# 467444_130_3_2.net
KiCad netlist of a schematic drawn in Altium Designer
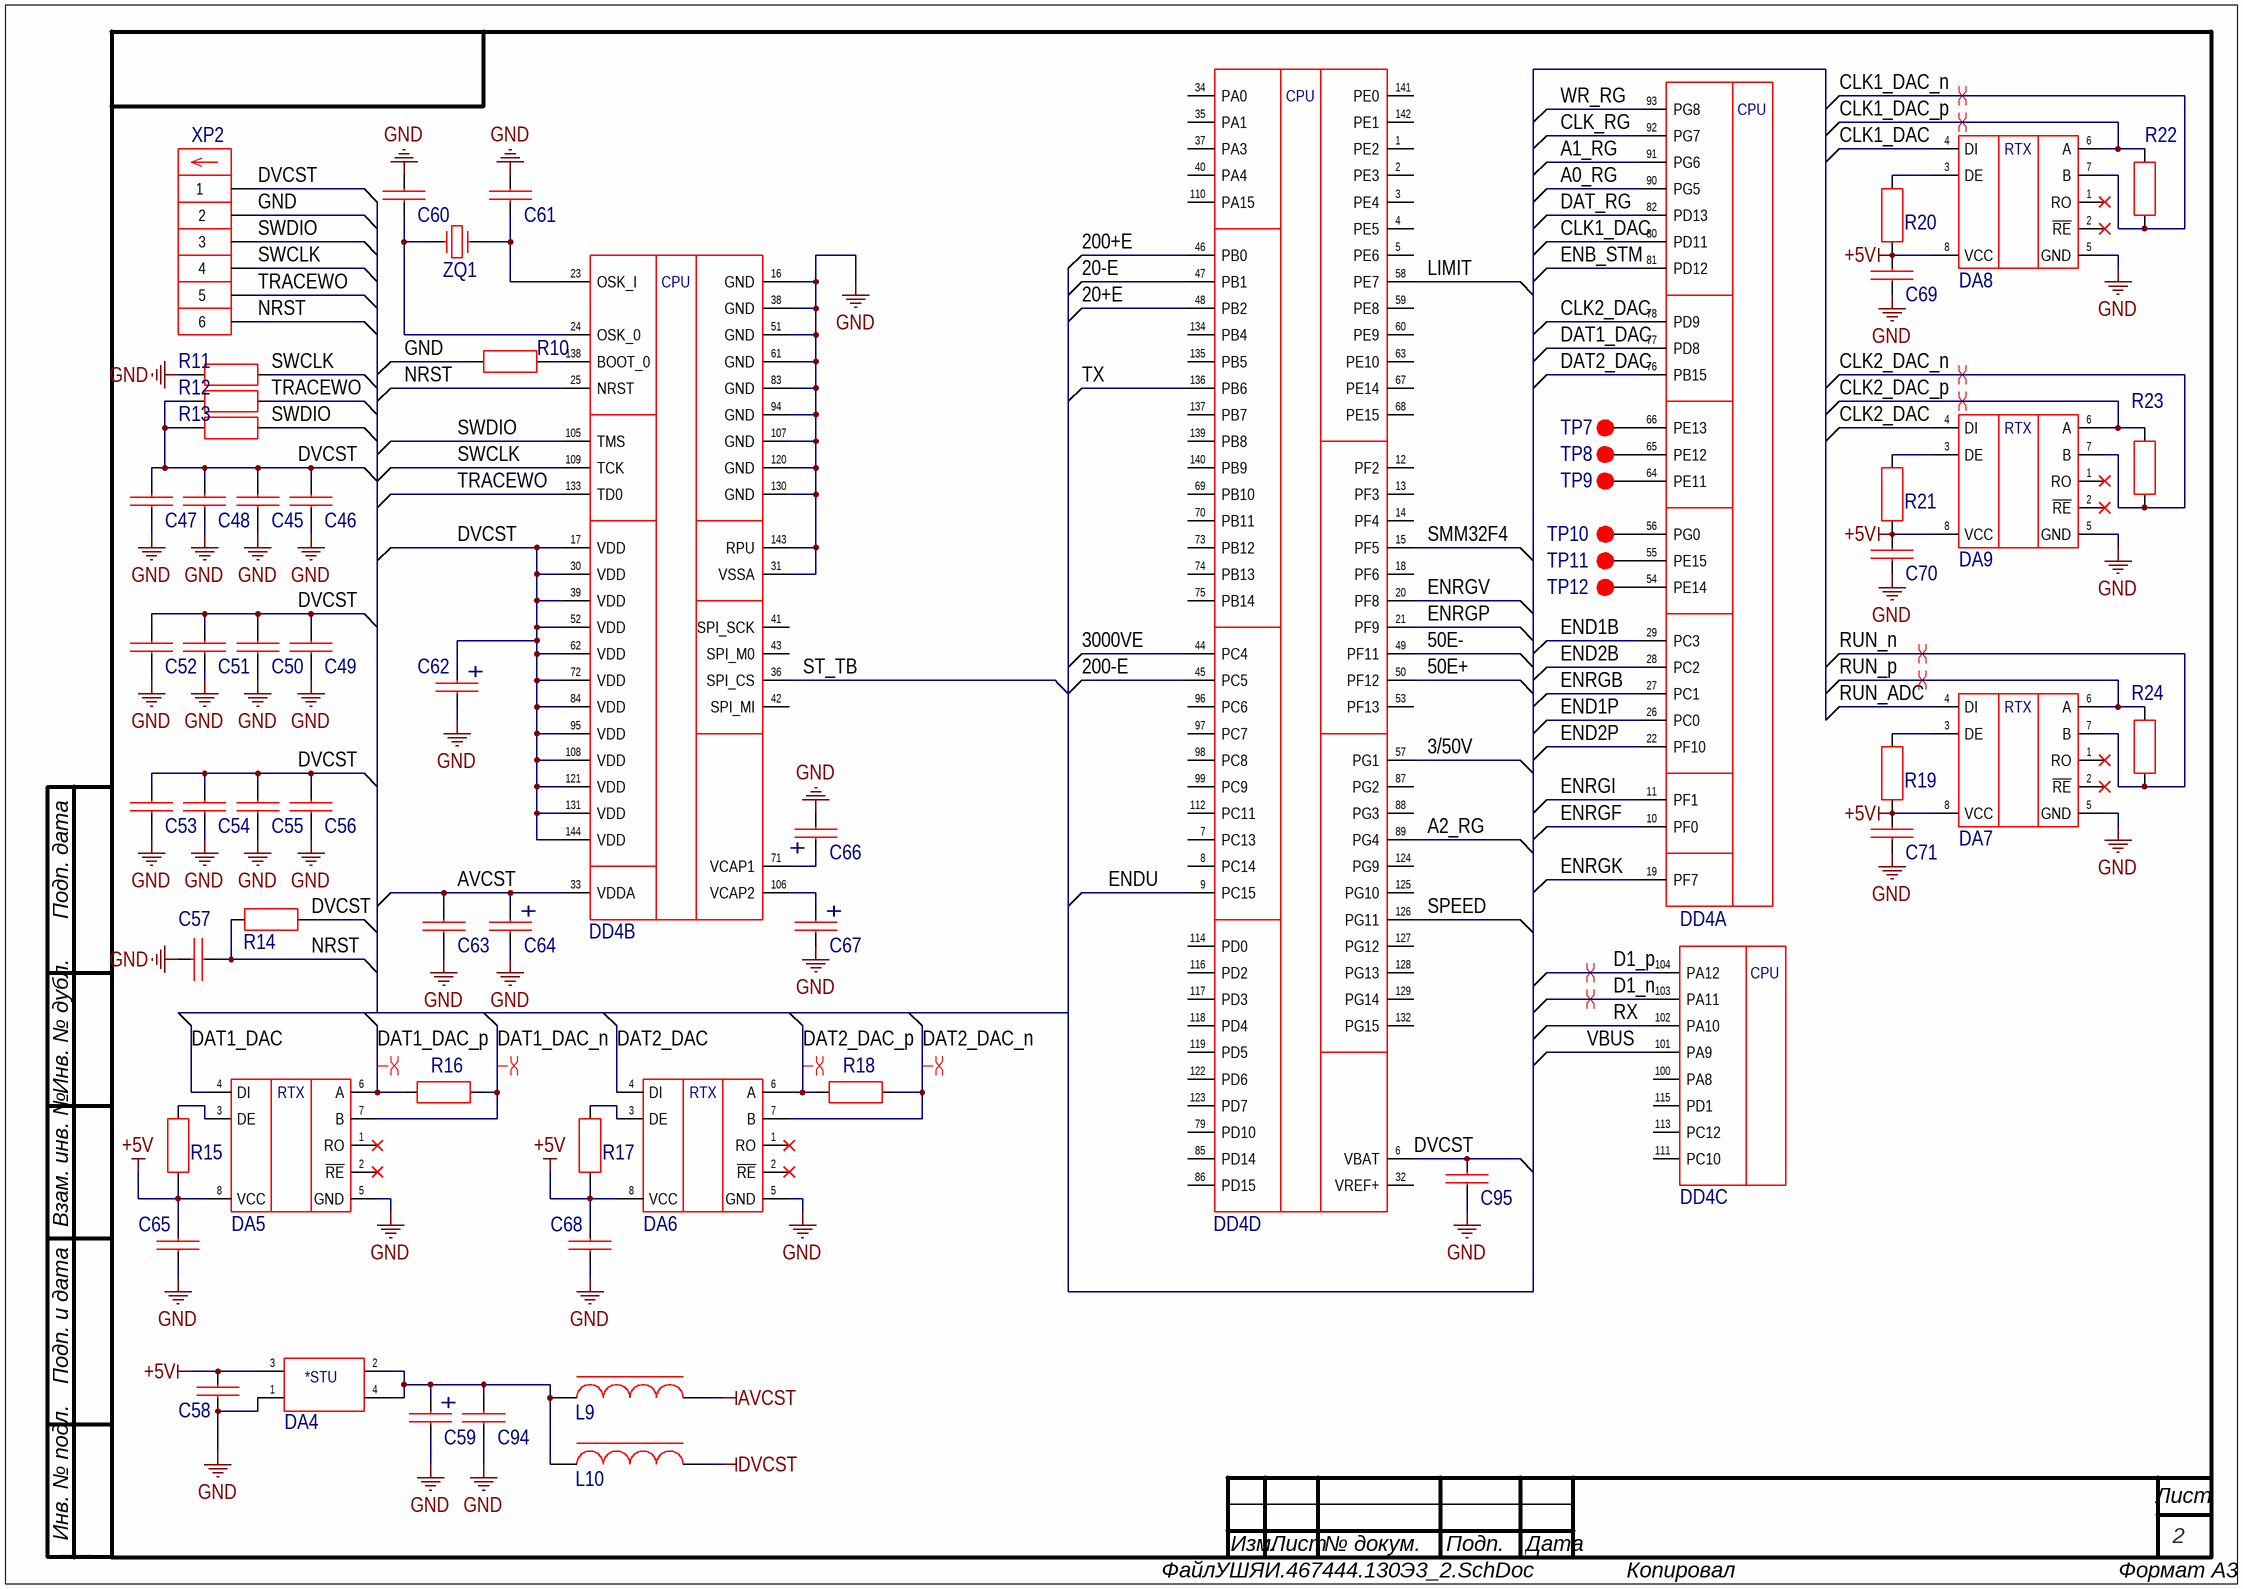
[diagram p0: УШЯИ.467444.130Э3_2.SchDoc]

(export (version "E")
  (design (tool "Eeschema 10.0.6"))
  (components
    (comp (ref "C45")
      (value "0,1 µF")
      (footprint "C_0805 [2012 Metric]")
      (description "Неполярный конденсатор")
      (fields (field (name "MANUFACTURER") "Murata") (field (name "VOLTAGE") "50V"))
      (libsource (lib "lib") (part "C_const"))
    )
    (comp (ref "C46")
      (value "0,1 µF")
      (footprint "C_0805 [2012 Metric]")
      (description "Неполярный конденсатор")
      (fields (field (name "MANUFACTURER") "Murata") (field (name "VOLTAGE") "50V"))
      (libsource (lib "lib") (part "C_const"))
    )
    (comp (ref "C47")
      (value "0,1 µF")
      (footprint "C_0805 [2012 Metric]")
      (description "Неполярный конденсатор")
      (fields (field (name "MANUFACTURER") "Murata") (field (name "VOLTAGE") "50V"))
      (libsource (lib "lib") (part "C_const"))
    )
    (comp (ref "C48")
      (value "0,1 µF")
      (footprint "C_0805 [2012 Metric]")
      (description "Неполярный конденсатор")
      (fields (field (name "MANUFACTURER") "Murata") (field (name "VOLTAGE") "50V"))
      (libsource (lib "lib") (part "C_const"))
    )
    (comp (ref "C49")
      (value "0,1 µF")
      (footprint "C_0805 [2012 Metric]")
      (description "Неполярный конденсатор")
      (fields (field (name "MANUFACTURER") "Murata") (field (name "VOLTAGE") "50V"))
      (libsource (lib "lib") (part "C_const"))
    )
    (comp (ref "C50")
      (value "0,1 µF")
      (footprint "C_0805 [2012 Metric]")
      (description "Неполярный конденсатор")
      (fields (field (name "MANUFACTURER") "Murata") (field (name "VOLTAGE") "50V"))
      (libsource (lib "lib") (part "C_const"))
    )
    (comp (ref "C51")
      (value "0,1 µF")
      (footprint "C_0805 [2012 Metric]")
      (description "Неполярный конденсатор")
      (fields (field (name "MANUFACTURER") "Murata") (field (name "VOLTAGE") "50V"))
      (libsource (lib "lib") (part "C_const"))
    )
    (comp (ref "C52")
      (value "0,1 µF")
      (footprint "C_0805 [2012 Metric]")
      (description "Неполярный конденсатор")
      (fields (field (name "MANUFACTURER") "Murata") (field (name "VOLTAGE") "50V"))
      (libsource (lib "lib") (part "C_const"))
    )
    (comp (ref "C53")
      (value "0,1 µF")
      (footprint "C_0805 [2012 Metric]")
      (description "Неполярный конденсатор")
      (fields (field (name "MANUFACTURER") "Murata") (field (name "VOLTAGE") "50V"))
      (libsource (lib "lib") (part "C_const"))
    )
    (comp (ref "C54")
      (value "0,1 µF")
      (footprint "C_0805 [2012 Metric]")
      (description "Неполярный конденсатор")
      (fields (field (name "MANUFACTURER") "Murata") (field (name "VOLTAGE") "50V"))
      (libsource (lib "lib") (part "C_const"))
    )
    (comp (ref "C55")
      (value "0,1 µF")
      (footprint "C_0805 [2012 Metric]")
      (description "Неполярный конденсатор")
      (fields (field (name "MANUFACTURER") "Murata") (field (name "VOLTAGE") "50V"))
      (libsource (lib "lib") (part "C_const"))
    )
    (comp (ref "C56")
      (value "0,1 µF")
      (footprint "C_0805 [2012 Metric]")
      (description "Неполярный конденсатор")
      (fields (field (name "MANUFACTURER") "Murata") (field (name "VOLTAGE") "50V"))
      (libsource (lib "lib") (part "C_const"))
    )
    (comp (ref "C57")
      (value "0,1 µF")
      (footprint "C_0805 [2012 Metric]")
      (description "Неполярный конденсатор")
      (fields (field (name "MANUFACTURER") "Murata") (field (name "VOLTAGE") "50V"))
      (libsource (lib "lib") (part "C_const"))
    )
    (comp (ref "C58")
      (value "0,1 µF")
      (footprint "C_0805 [2012 Metric]")
      (description "Неполярный конденсатор")
      (fields (field (name "MANUFACTURER") "Murata") (field (name "VOLTAGE") "50V"))
      (libsource (lib "lib") (part "C_const"))
    )
    (comp (ref "C59")
      (value "4,7 µF")
      (footprint "C+_1210 [3528-21 Metric]")
      (description "Полярный конденсатор")
      (fields (field (name "MANUFACTURER") "KYOCERA AVX") (field (name "VOLTAGE") "20V\r\n10V"))
      (libsource (lib "lib") (part "C_electrolytic"))
    )
    (comp (ref "C60")
      (value "20 pF")
      (footprint "C_0805 [2012 Metric]")
      (description "Неполярный конденсатор")
      (fields (field (name "MANUFACTURER") "Murata") (field (name "VOLTAGE") "50V"))
      (libsource (lib "lib") (part "C_const"))
    )
    (comp (ref "C61")
      (value "20 pF")
      (footprint "C_0805 [2012 Metric]")
      (description "Неполярный конденсатор")
      (fields (field (name "MANUFACTURER") "Murata") (field (name "VOLTAGE") "50V"))
      (libsource (lib "lib") (part "C_const"))
    )
    (comp (ref "C62")
      (value "10 µF")
      (footprint "C+_1210 [3528-21 Metric]")
      (description "Полярный конденсатор")
      (fields (field (name "MANUFACTURER") "KYOCERA AVX") (field (name "VOLTAGE") "20V\r\n10V"))
      (libsource (lib "lib") (part "C_electrolytic"))
    )
    (comp (ref "C63")
      (value "0,1 µF")
      (footprint "C_0805 [2012 Metric]")
      (description "Неполярный конденсатор")
      (fields (field (name "MANUFACTURER") "Murata") (field (name "VOLTAGE") "50V"))
      (libsource (lib "lib") (part "C_const"))
    )
    (comp (ref "C64")
      (value "10 µF")
      (footprint "C+_1210 [3528-21 Metric]")
      (description "Полярный конденсатор")
      (fields (field (name "MANUFACTURER") "KYOCERA AVX") (field (name "VOLTAGE") "20V\r\n10V"))
      (libsource (lib "lib") (part "C_electrolytic"))
    )
    (comp (ref "C65")
      (value "0,1 µF")
      (footprint "C_0805 [2012 Metric]")
      (description "Неполярный конденсатор")
      (fields (field (name "MANUFACTURER") "Murata") (field (name "VOLTAGE") "50V"))
      (libsource (lib "lib") (part "C_const"))
    )
    (comp (ref "C66")
      (value "2,2 µF")
      (footprint "C+_1206 [3216-18 Metric]")
      (description "Полярный конденсатор")
      (fields (field (name "MANUFACTURER") "AVX") (field (name "VOLTAGE") "16V\r\n10V"))
      (libsource (lib "lib") (part "C_electrolytic"))
    )
    (comp (ref "C67")
      (value "2,2 µF")
      (footprint "C+_1206 [3216-18 Metric]")
      (description "Полярный конденсатор")
      (fields (field (name "MANUFACTURER") "AVX") (field (name "VOLTAGE") "16V\r\n10V"))
      (libsource (lib "lib") (part "C_electrolytic"))
    )
    (comp (ref "C68")
      (value "0,1 µF")
      (footprint "C_0805 [2012 Metric]")
      (description "Неполярный конденсатор")
      (fields (field (name "MANUFACTURER") "Murata") (field (name "VOLTAGE") "50V"))
      (libsource (lib "lib") (part "C_const"))
    )
    (comp (ref "C69")
      (value "0,1 µF")
      (footprint "C_0805 [2012 Metric]")
      (description "Неполярный конденсатор")
      (fields (field (name "MANUFACTURER") "Murata") (field (name "VOLTAGE") "50V"))
      (libsource (lib "lib") (part "C_const"))
    )
    (comp (ref "C70")
      (value "0,1 µF")
      (footprint "C_0805 [2012 Metric]")
      (description "Неполярный конденсатор")
      (fields (field (name "MANUFACTURER") "Murata") (field (name "VOLTAGE") "50V"))
      (libsource (lib "lib") (part "C_const"))
    )
    (comp (ref "C71")
      (value "0,1 µF")
      (footprint "C_0805 [2012 Metric]")
      (description "Неполярный конденсатор")
      (fields (field (name "MANUFACTURER") "Murata") (field (name "VOLTAGE") "50V"))
      (libsource (lib "lib") (part "C_const"))
    )
    (comp (ref "C94")
      (value "0,1 µF")
      (footprint "C_0805 [2012 Metric]")
      (description "Неполярный конденсатор")
      (fields (field (name "MANUFACTURER") "Murata") (field (name "VOLTAGE") "25V"))
      (libsource (lib "lib") (part "C_const"))
    )
    (comp (ref "C95")
      (value "0,1 µF")
      (footprint "C_0805 [2012 Metric]")
      (description "Неполярный конденсатор")
      (fields (field (name "MANUFACTURER") "Murata") (field (name "VOLTAGE") "50V"))
      (libsource (lib "lib") (part "C_const"))
    )
    (comp (ref "DA4")
      (value "LD1117AS33TR")
      (footprint "SOT-223")
      (description "IC, Fixed LDO Voltage Regulator, 5.3V to 10V, 1.15V Dropout, 3.3Vout, 1Aout")
      (fields (field (name "MANUFACTURER") "STMicroelectronics"))
      (libsource (lib "lib") (part "VolReg_LD1117AS33TR"))
    )
    (comp (ref "DA5")
      (value "ADM483AR")
      (footprint "SOIC-8_1.27_5x4x1.75")
      (description "IC, Transceiver, RS422/RS485, 1 Driver, 1 Receiver, 4.75 V to 5.25 V, -40°C to 125°C")
      (fields (field (name "MANUFACTURER") "Analog Devices"))
      (libsource (lib "lib") (part "ADM483"))
    )
    (comp (ref "DA6")
      (value "ADM483AR")
      (footprint "SOIC-8_1.27_5x4x1.75")
      (description "IC, Transceiver, RS422/RS485, 1 Driver, 1 Receiver, 4.75 V to 5.25 V, -40°C to 125°C")
      (fields (field (name "MANUFACTURER") "Analog Devices"))
      (libsource (lib "lib") (part "ADM483"))
    )
    (comp (ref "DA7")
      (value "ADM483AR")
      (footprint "SOIC-8_1.27_5x4x1.75")
      (description "IC, Transceiver, RS422/RS485, 1 Driver, 1 Receiver, 4.75 V to 5.25 V, -40°C to 125°C")
      (fields (field (name "MANUFACTURER") "Analog Devices"))
      (libsource (lib "lib") (part "ADM483"))
    )
    (comp (ref "DA8")
      (value "ADM483AR")
      (footprint "SOIC-8_1.27_5x4x1.75")
      (description "IC, Transceiver, RS422/RS485, 1 Driver, 1 Receiver, 4.75 V to 5.25 V, -40°C to 125°C")
      (fields (field (name "MANUFACTURER") "Analog Devices"))
      (libsource (lib "lib") (part "ADM483"))
    )
    (comp (ref "DA9")
      (value "ADM483AR")
      (footprint "SOIC-8_1.27_5x4x1.75")
      (description "IC, Transceiver, RS422/RS485, 1 Driver, 1 Receiver, 4.75 V to 5.25 V, -40°C to 125°C")
      (fields (field (name "MANUFACTURER") "Analog Devices"))
      (libsource (lib "lib") (part "ADM483"))
    )
    (comp (ref "DD4")
      (value "STM32F429VIT6STM32F407ZGTx")
      (footprint "QFP-144[20x20]_0.5_22x22x1.6")
      (description "IC, ARM Cortex-M4, 168 MHz, 1 MB ROM, 192 kB RAM, -40°C to 85°C")
      (fields (field (name "MANUFACTURER") "STMicroelectronics"))
      (libsource (lib "") (part "STM32F407_1"))
    )
    (comp (ref "L9")
      (value "~")
      (footprint "IND_0805 [2012 Metric]")
      (fields (field (name "MANUFACTURER") "Vishay") (field (name "TOLERANCE") "±25%"))
      (libsource (lib "lib") (part "IND_ferromagnetic/ferrite_core"))
    )
    (comp (ref "L10")
      (value "~")
      (footprint "IND_0805 [2012 Metric]")
      (fields (field (name "MANUFACTURER") "Vishay") (field (name "TOLERANCE") "±25%"))
      (libsource (lib "lib") (part "IND_ferromagnetic/ferrite_core"))
    )
    (comp (ref "R10")
      (value "10k")
      (footprint "R_0805 [2012 Metric]")
      (fields (field (name "TOLERANCE") "±5%"))
      (libsource (lib "lib") (part "R_Const"))
    )
    (comp (ref "R11")
      (value "10k")
      (footprint "R_0805 [2012 Metric]")
      (fields (field (name "TOLERANCE") "±5%"))
      (libsource (lib "lib") (part "R_Const"))
    )
    (comp (ref "R12")
      (value "10k")
      (footprint "R_0805 [2012 Metric]")
      (fields (field (name "TOLERANCE") "±5%"))
      (libsource (lib "lib") (part "R_Const"))
    )
    (comp (ref "R13")
      (value "10k")
      (footprint "R_0805 [2012 Metric]")
      (fields (field (name "TOLERANCE") "±5%"))
      (libsource (lib "lib") (part "R_Const"))
    )
    (comp (ref "R14")
      (value "10k")
      (footprint "R_0805 [2012 Metric]")
      (fields (field (name "TOLERANCE") "±5%"))
      (libsource (lib "lib") (part "R_Const"))
    )
    (comp (ref "R15")
      (value "10k")
      (footprint "R_0805 [2012 Metric]")
      (fields (field (name "TOLERANCE") "±5%"))
      (libsource (lib "lib") (part "R_Const"))
    )
    (comp (ref "R16")
      (value "100R")
      (footprint "R_0805 [2012 Metric]")
      (fields (field (name "TOLERANCE") "±5%"))
      (libsource (lib "lib") (part "R_Const"))
    )
    (comp (ref "R17")
      (value "10k")
      (footprint "R_0805 [2012 Metric]")
      (fields (field (name "TOLERANCE") "±5%"))
      (libsource (lib "lib") (part "R_Const"))
    )
    (comp (ref "R18")
      (value "100R")
      (footprint "R_0805 [2012 Metric]")
      (fields (field (name "TOLERANCE") "±5%"))
      (libsource (lib "lib") (part "R_Const"))
    )
    (comp (ref "R19")
      (value "10k")
      (footprint "R_0805 [2012 Metric]")
      (fields (field (name "TOLERANCE") "±5%"))
      (libsource (lib "lib") (part "R_Const"))
    )
    (comp (ref "R20")
      (value "10k")
      (footprint "R_0805 [2012 Metric]")
      (fields (field (name "TOLERANCE") "±5%"))
      (libsource (lib "lib") (part "R_Const"))
    )
    (comp (ref "R21")
      (value "10k")
      (footprint "R_0805 [2012 Metric]")
      (fields (field (name "TOLERANCE") "±5%"))
      (libsource (lib "lib") (part "R_Const"))
    )
    (comp (ref "R22")
      (value "100R")
      (footprint "R_0805 [2012 Metric]")
      (fields (field (name "TOLERANCE") "±5%"))
      (libsource (lib "lib") (part "R_Const"))
    )
    (comp (ref "R23")
      (value "100R")
      (footprint "R_0805 [2012 Metric]")
      (fields (field (name "TOLERANCE") "±5%"))
      (libsource (lib "lib") (part "R_Const"))
    )
    (comp (ref "R24")
      (value "100R")
      (footprint "R_0805 [2012 Metric]")
      (fields (field (name "TOLERANCE") "±5%"))
      (libsource (lib "lib") (part "R_Const"))
    )
    (comp (ref "TP7") (value "~") (footprint "DSP_1.3") (libsource (lib "lib") (part "TP")))
    (comp (ref "TP8") (value "~") (footprint "DSP_1.3") (libsource (lib "lib") (part "TP")))
    (comp (ref "TP9") (value "~") (footprint "DSP_1.3") (libsource (lib "lib") (part "TP")))
    (comp (ref "TP10") (value "~") (footprint "DSP_1.3") (libsource (lib "lib") (part "TP")))
    (comp (ref "TP11") (value "~") (footprint "DSP_1.3") (libsource (lib "lib") (part "TP")))
    (comp (ref "TP12") (value "~") (footprint "DSP_1.3") (libsource (lib "lib") (part "TP")))
    (comp (ref "XP2")
      (value "AMPMODU II 280372-2")
      (footprint "AMP II-280372-2")
      (description "Male, 6 pin, 1 row, Vertical, Board-to-Board, 2.54 mm")
      (fields (field (name "MANUFACTURER") "TE Connectivity"))
      (libsource (lib "lib") (part "M_6"))
    )
    (comp (ref "ZQ1")
      (value "Q 25.0JXS63-12-30/30-FU")
      (footprint "JXS63")
      (fields (field (name "MANUFACTURER") "Jauch Quartz GmbH"))
      (libsource (lib "lib") (part "Rezonator_JXS63"))
    )
  )
  (nets
    (net (code "1") (name "+5V") (class "Default")
      (node (ref "C58") (pin "1") (pinfunction "1_1") (pintype "passive"))
      (node (ref "C65") (pin "2") (pinfunction "2_2") (pintype "passive"))
      (node (ref "C68") (pin "2") (pinfunction "2_2") (pintype "passive"))
      (node (ref "C69") (pin "2") (pinfunction "2_2") (pintype "passive"))
      (node (ref "C70") (pin "2") (pinfunction "2_2") (pintype "passive"))
      (node (ref "C71") (pin "2") (pinfunction "2_2") (pintype "passive"))
      (node (ref "DA4") (pin "3") (pinfunction "VIN_3") (pintype "passive"))
      (node (ref "DA5") (pin "8") (pinfunction "VCC_8") (pintype "passive"))
      (node (ref "DA6") (pin "8") (pinfunction "VCC_8") (pintype "passive"))
      (node (ref "DA7") (pin "8") (pinfunction "VCC_8") (pintype "passive"))
      (node (ref "DA8") (pin "8") (pinfunction "VCC_8") (pintype "passive"))
      (node (ref "DA9") (pin "8") (pinfunction "VCC_8") (pintype "passive"))
      (node (ref "R15") (pin "1") (pinfunction "1_1") (pintype "passive"))
      (node (ref "R17") (pin "1") (pinfunction "1_1") (pintype "passive"))
      (node (ref "R19") (pin "1") (pinfunction "1_1") (pintype "passive"))
      (node (ref "R20") (pin "1") (pinfunction "1_1") (pintype "passive"))
      (node (ref "R21") (pin "1") (pinfunction "1_1") (pintype "passive"))
    )
    (net (code "2") (name "/3{slash}50V") (class "Default")
      (node (ref "DD4") (pin "57") (pinfunction "PG1_57") (pintype "passive"))
    )
    (net (code "3") (name "/20+E") (class "Default")
      (node (ref "DD4") (pin "48") (pinfunction "PB2_48") (pintype "passive"))
    )
    (net (code "4") (name "/20-E") (class "Default")
      (node (ref "DD4") (pin "47") (pinfunction "PB1_47") (pintype "passive"))
    )
    (net (code "5") (name "/50E+") (class "Default")
      (node (ref "DD4") (pin "50") (pinfunction "PF12_50") (pintype "passive"))
    )
    (net (code "6") (name "/50E-") (class "Default")
      (node (ref "DD4") (pin "49") (pinfunction "PF11_49") (pintype "passive"))
    )
    (net (code "7") (name "/200+E") (class "Default")
      (node (ref "DD4") (pin "46") (pinfunction "PB0_46") (pintype "passive"))
    )
    (net (code "8") (name "/200-E") (class "Default")
      (node (ref "DD4") (pin "45") (pinfunction "PC5_45") (pintype "passive"))
    )
    (net (code "9") (name "/3000VE") (class "Default")
      (node (ref "DD4") (pin "44") (pinfunction "PC4_44") (pintype "passive"))
    )
    (net (code "10") (name "/A0_RG") (class "Default")
      (node (ref "DD4") (pin "90") (pinfunction "PG5_90") (pintype "passive"))
    )
    (net (code "11") (name "/A1_RG") (class "Default")
      (node (ref "DD4") (pin "91") (pinfunction "PG6_91") (pintype "passive"))
    )
    (net (code "12") (name "/A2_RG") (class "Default")
      (node (ref "DD4") (pin "89") (pinfunction "PG4_89") (pintype "passive"))
    )
    (net (code "13") (name "/CLK1_DAC") (class "Default")
      (node (ref "DA8") (pin "4") (pinfunction "DI_4") (pintype "passive"))
      (node (ref "DD4") (pin "80") (pinfunction "PD11_80") (pintype "passive"))
    )
    (net (code "14") (name "/CLK1_DAC_n") (class "Default")
      (node (ref "DA8") (pin "7") (pinfunction "B_7") (pintype "passive"))
      (node (ref "R22") (pin "1") (pinfunction "1_1") (pintype "passive"))
    )
    (net (code "15") (name "/CLK1_DAC_p") (class "Default")
      (node (ref "DA8") (pin "6") (pinfunction "A_6") (pintype "passive"))
      (node (ref "R22") (pin "2") (pinfunction "2_2") (pintype "passive"))
    )
    (net (code "16") (name "/CLK2_DAC") (class "Default")
      (node (ref "DA9") (pin "4") (pinfunction "DI_4") (pintype "passive"))
      (node (ref "DD4") (pin "78") (pinfunction "PD9_78") (pintype "passive"))
    )
    (net (code "17") (name "/CLK2_DAC_n") (class "Default")
      (node (ref "DA9") (pin "7") (pinfunction "B_7") (pintype "passive"))
      (node (ref "R23") (pin "1") (pinfunction "1_1") (pintype "passive"))
    )
    (net (code "18") (name "/CLK2_DAC_p") (class "Default")
      (node (ref "DA9") (pin "6") (pinfunction "A_6") (pintype "passive"))
      (node (ref "R23") (pin "2") (pinfunction "2_2") (pintype "passive"))
    )
    (net (code "19") (name "/CLK_RG") (class "Default")
      (node (ref "DD4") (pin "92") (pinfunction "PG7_92") (pintype "passive"))
    )
    (net (code "20") (name "/D1_n") (class "Default")
      (node (ref "DD4") (pin "103") (pinfunction "PA11_103") (pintype "passive"))
    )
    (net (code "21") (name "/D1_p") (class "Default")
      (node (ref "DD4") (pin "104") (pinfunction "PA12_104") (pintype "passive"))
    )
    (net (code "22") (name "/DAT1_DAC") (class "Default")
      (node (ref "DA5") (pin "4") (pinfunction "DI_4") (pintype "passive"))
      (node (ref "DD4") (pin "77") (pinfunction "PD8_77") (pintype "passive"))
    )
    (net (code "23") (name "/DAT1_DAC_n") (class "Default")
      (node (ref "DA5") (pin "7") (pinfunction "B_7") (pintype "passive"))
      (node (ref "R16") (pin "2") (pinfunction "2_2") (pintype "passive"))
    )
    (net (code "24") (name "/DAT1_DAC_p") (class "Default")
      (node (ref "DA5") (pin "6") (pinfunction "A_6") (pintype "passive"))
      (node (ref "R16") (pin "1") (pinfunction "1_1") (pintype "passive"))
    )
    (net (code "25") (name "/DAT2_DAC") (class "Default")
      (node (ref "DA6") (pin "4") (pinfunction "DI_4") (pintype "passive"))
      (node (ref "DD4") (pin "76") (pinfunction "PB15_76") (pintype "passive"))
    )
    (net (code "26") (name "/DAT2_DAC_n") (class "Default")
      (node (ref "DA6") (pin "7") (pinfunction "B_7") (pintype "passive"))
      (node (ref "R18") (pin "2") (pinfunction "2_2") (pintype "passive"))
    )
    (net (code "27") (name "/DAT2_DAC_p") (class "Default")
      (node (ref "DA6") (pin "6") (pinfunction "A_6") (pintype "passive"))
      (node (ref "R18") (pin "1") (pinfunction "1_1") (pintype "passive"))
    )
    (net (code "28") (name "/DAT_RG") (class "Default")
      (node (ref "DD4") (pin "82") (pinfunction "PD13_82") (pintype "passive"))
    )
    (net (code "29") (name "/ENB_STM") (class "Default")
      (node (ref "DD4") (pin "81") (pinfunction "PD12_81") (pintype "passive"))
    )
    (net (code "30") (name "/END1B") (class "Default")
      (node (ref "DD4") (pin "29") (pinfunction "PC3_29") (pintype "passive"))
    )
    (net (code "31") (name "/END1P") (class "Default")
      (node (ref "DD4") (pin "26") (pinfunction "PC0_26") (pintype "passive"))
    )
    (net (code "32") (name "/END2B") (class "Default")
      (node (ref "DD4") (pin "28") (pinfunction "PC2_28") (pintype "passive"))
    )
    (net (code "33") (name "/END2P") (class "Default")
      (node (ref "DD4") (pin "22") (pinfunction "PF10_22") (pintype "passive"))
    )
    (net (code "34") (name "/ENDU") (class "Default")
      (node (ref "DD4") (pin "9") (pinfunction "PC15_9") (pintype "passive"))
    )
    (net (code "35") (name "/ENRGB") (class "Default")
      (node (ref "DD4") (pin "27") (pinfunction "PC1_27") (pintype "passive"))
    )
    (net (code "36") (name "/ENRGF") (class "Default")
      (node (ref "DD4") (pin "10") (pinfunction "PF0_10") (pintype "passive"))
    )
    (net (code "37") (name "/ENRGI") (class "Default")
      (node (ref "DD4") (pin "11") (pinfunction "PF1_11") (pintype "passive"))
    )
    (net (code "38") (name "/ENRGK") (class "Default")
      (node (ref "DD4") (pin "19") (pinfunction "PF7_19") (pintype "passive"))
    )
    (net (code "39") (name "/ENRGP") (class "Default")
      (node (ref "DD4") (pin "21") (pinfunction "PF9_21") (pintype "passive"))
    )
    (net (code "40") (name "/ENRGV") (class "Default")
      (node (ref "DD4") (pin "20") (pinfunction "PF8_20") (pintype "passive"))
    )
    (net (code "41") (name "/LIMIT") (class "Default")
      (node (ref "DD4") (pin "58") (pinfunction "PE7_58") (pintype "passive"))
    )
    (net (code "42") (name "/NRST") (class "Default")
      (node (ref "C57") (pin "2") (pinfunction "2_2") (pintype "passive"))
      (node (ref "DD4") (pin "25") (pinfunction "NRST_25") (pintype "passive"))
      (node (ref "R14") (pin "2") (pinfunction "2_2") (pintype "passive"))
      (node (ref "XP2") (pin "6") (pinfunction "6_6") (pintype "passive"))
    )
    (net (code "43") (name "/RUN_ADC") (class "Default")
      (node (ref "DA7") (pin "4") (pinfunction "DI_4") (pintype "passive"))
    )
    (net (code "44") (name "/RUN_n") (class "Default")
      (node (ref "DA7") (pin "7") (pinfunction "B_7") (pintype "passive"))
      (node (ref "R24") (pin "1") (pinfunction "1_1") (pintype "passive"))
    )
    (net (code "45") (name "/RUN_p") (class "Default")
      (node (ref "DA7") (pin "6") (pinfunction "A_6") (pintype "passive"))
      (node (ref "R24") (pin "2") (pinfunction "2_2") (pintype "passive"))
    )
    (net (code "46") (name "/RX") (class "Default")
      (node (ref "DD4") (pin "102") (pinfunction "PA10_102") (pintype "passive"))
    )
    (net (code "47") (name "/SMM32F4") (class "Default")
      (node (ref "DD4") (pin "15") (pinfunction "PF5_15") (pintype "passive"))
    )
    (net (code "48") (name "/SPEED") (class "Default")
      (node (ref "DD4") (pin "126") (pinfunction "PG11_126") (pintype "passive"))
    )
    (net (code "49") (name "/ST_TB") (class "Default")
      (node (ref "DD4") (pin "36") (pinfunction "SPI_CS_36") (pintype "passive"))
    )
    (net (code "50") (name "/SWCLK") (class "Default")
      (node (ref "DD4") (pin "109") (pinfunction "TCK_109") (pintype "passive"))
      (node (ref "R11") (pin "2") (pinfunction "2_2") (pintype "passive"))
      (node (ref "XP2") (pin "4") (pinfunction "4_4") (pintype "passive"))
    )
    (net (code "51") (name "/SWDIO") (class "Default")
      (node (ref "DD4") (pin "105") (pinfunction "TMS_105") (pintype "passive"))
      (node (ref "R13") (pin "2") (pinfunction "2_2") (pintype "passive"))
      (node (ref "XP2") (pin "3") (pinfunction "3_3") (pintype "passive"))
    )
    (net (code "52") (name "/TRACEWO") (class "Default")
      (node (ref "DD4") (pin "133") (pinfunction "TD0_133") (pintype "passive"))
      (node (ref "R12") (pin "2") (pinfunction "2_2") (pintype "passive"))
      (node (ref "XP2") (pin "5") (pinfunction "5_5") (pintype "passive"))
    )
    (net (code "53") (name "/TX") (class "Default")
      (node (ref "DD4") (pin "136") (pinfunction "PB6_136") (pintype "passive"))
    )
    (net (code "54") (name "/VBUS") (class "Default")
      (node (ref "DD4") (pin "101") (pinfunction "PA9_101") (pintype "passive"))
    )
    (net (code "55") (name "/WR_RG") (class "Default")
      (node (ref "DD4") (pin "93") (pinfunction "PG8_93") (pintype "passive"))
    )
    (net (code "56") (name "AVCST") (class "Default")
      (node (ref "C63") (pin "2") (pinfunction "2_2") (pintype "passive"))
      (node (ref "C64") (pin "+") (pinfunction "+_+") (pintype "passive"))
      (node (ref "DD4") (pin "33") (pinfunction "VDDA_33") (pintype "passive"))
      (node (ref "L9") (pin "2") (pinfunction "2_2") (pintype "passive"))
    )
    (net (code "57") (name "DVCST") (class "Default")
      (node (ref "C45") (pin "2") (pinfunction "2_2") (pintype "passive"))
      (node (ref "C46") (pin "2") (pinfunction "2_2") (pintype "passive"))
      (node (ref "C47") (pin "2") (pinfunction "2_2") (pintype "passive"))
      (node (ref "C48") (pin "2") (pinfunction "2_2") (pintype "passive"))
      (node (ref "C49") (pin "2") (pinfunction "2_2") (pintype "passive"))
      (node (ref "C50") (pin "2") (pinfunction "2_2") (pintype "passive"))
      (node (ref "C51") (pin "2") (pinfunction "2_2") (pintype "passive"))
      (node (ref "C52") (pin "2") (pinfunction "2_2") (pintype "passive"))
      (node (ref "C53") (pin "2") (pinfunction "2_2") (pintype "passive"))
      (node (ref "C54") (pin "2") (pinfunction "2_2") (pintype "passive"))
      (node (ref "C55") (pin "2") (pinfunction "2_2") (pintype "passive"))
      (node (ref "C56") (pin "2") (pinfunction "2_2") (pintype "passive"))
      (node (ref "C62") (pin "+") (pinfunction "+_+") (pintype "passive"))
      (node (ref "C95") (pin "2") (pinfunction "2_2") (pintype "passive"))
      (node (ref "DD4") (pin "108") (pinfunction "VDD_108") (pintype "passive"))
      (node (ref "DD4") (pin "121") (pinfunction "VDD_121") (pintype "passive"))
      (node (ref "DD4") (pin "131") (pinfunction "VDD_131") (pintype "passive"))
      (node (ref "DD4") (pin "144") (pinfunction "VDD_144") (pintype "passive"))
      (node (ref "DD4") (pin "17") (pinfunction "VDD_17") (pintype "passive"))
      (node (ref "DD4") (pin "30") (pinfunction "VDD_30") (pintype "passive"))
      (node (ref "DD4") (pin "39") (pinfunction "VDD_39") (pintype "passive"))
      (node (ref "DD4") (pin "52") (pinfunction "VDD_52") (pintype "passive"))
      (node (ref "DD4") (pin "6") (pinfunction "VBAT_6") (pintype "passive"))
      (node (ref "DD4") (pin "62") (pinfunction "VDD_62") (pintype "passive"))
      (node (ref "DD4") (pin "72") (pinfunction "VDD_72") (pintype "passive"))
      (node (ref "DD4") (pin "84") (pinfunction "VDD_84") (pintype "passive"))
      (node (ref "DD4") (pin "95") (pinfunction "VDD_95") (pintype "passive"))
      (node (ref "L10") (pin "2") (pinfunction "2_2") (pintype "passive"))
      (node (ref "R12") (pin "1") (pinfunction "1_1") (pintype "passive"))
      (node (ref "R13") (pin "1") (pinfunction "1_1") (pintype "passive"))
      (node (ref "R14") (pin "1") (pinfunction "1_1") (pintype "passive"))
      (node (ref "XP2") (pin "1") (pinfunction "1_1") (pintype "passive"))
    )
    (net (code "58") (name "GND") (class "Default")
      (node (ref "C45") (pin "1") (pinfunction "1_1") (pintype "passive"))
      (node (ref "C46") (pin "1") (pinfunction "1_1") (pintype "passive"))
      (node (ref "C47") (pin "1") (pinfunction "1_1") (pintype "passive"))
      (node (ref "C48") (pin "1") (pinfunction "1_1") (pintype "passive"))
      (node (ref "C49") (pin "1") (pinfunction "1_1") (pintype "passive"))
      (node (ref "C50") (pin "1") (pinfunction "1_1") (pintype "passive"))
      (node (ref "C51") (pin "1") (pinfunction "1_1") (pintype "passive"))
      (node (ref "C52") (pin "1") (pinfunction "1_1") (pintype "passive"))
      (node (ref "C53") (pin "1") (pinfunction "1_1") (pintype "passive"))
      (node (ref "C54") (pin "1") (pinfunction "1_1") (pintype "passive"))
      (node (ref "C55") (pin "1") (pinfunction "1_1") (pintype "passive"))
      (node (ref "C56") (pin "1") (pinfunction "1_1") (pintype "passive"))
      (node (ref "C57") (pin "1") (pinfunction "1_1") (pintype "passive"))
      (node (ref "C58") (pin "2") (pinfunction "2_2") (pintype "passive"))
      (node (ref "C59") (pin "-") (pinfunction "-_-") (pintype "passive"))
      (node (ref "C60") (pin "2") (pinfunction "2_2") (pintype "passive"))
      (node (ref "C61") (pin "2") (pinfunction "2_2") (pintype "passive"))
      (node (ref "C62") (pin "-") (pinfunction "-_-") (pintype "passive"))
      (node (ref "C63") (pin "1") (pinfunction "1_1") (pintype "passive"))
      (node (ref "C64") (pin "-") (pinfunction "-_-") (pintype "passive"))
      (node (ref "C65") (pin "1") (pinfunction "1_1") (pintype "passive"))
      (node (ref "C66") (pin "-") (pinfunction "-_-") (pintype "passive"))
      (node (ref "C67") (pin "-") (pinfunction "-_-") (pintype "passive"))
      (node (ref "C68") (pin "1") (pinfunction "1_1") (pintype "passive"))
      (node (ref "C69") (pin "1") (pinfunction "1_1") (pintype "passive"))
      (node (ref "C70") (pin "1") (pinfunction "1_1") (pintype "passive"))
      (node (ref "C71") (pin "1") (pinfunction "1_1") (pintype "passive"))
      (node (ref "C94") (pin "1") (pinfunction "1_1") (pintype "passive"))
      (node (ref "C95") (pin "1") (pinfunction "1_1") (pintype "passive"))
      (node (ref "DA4") (pin "1") (pinfunction "ADJ/GND_1") (pintype "passive"))
      (node (ref "DA5") (pin "5") (pinfunction "GND_5") (pintype "passive"))
      (node (ref "DA6") (pin "5") (pinfunction "GND_5") (pintype "passive"))
      (node (ref "DA7") (pin "5") (pinfunction "GND_5") (pintype "passive"))
      (node (ref "DA8") (pin "5") (pinfunction "GND_5") (pintype "passive"))
      (node (ref "DA9") (pin "5") (pinfunction "GND_5") (pintype "passive"))
      (node (ref "DD4") (pin "107") (pinfunction "GND_107") (pintype "passive"))
      (node (ref "DD4") (pin "120") (pinfunction "GND_120") (pintype "passive"))
      (node (ref "DD4") (pin "130") (pinfunction "GND_130") (pintype "passive"))
      (node (ref "DD4") (pin "143") (pinfunction "RPU_143") (pintype "passive"))
      (node (ref "DD4") (pin "16") (pinfunction "GND_16") (pintype "passive"))
      (node (ref "DD4") (pin "31") (pinfunction "VSSA_31") (pintype "passive"))
      (node (ref "DD4") (pin "38") (pinfunction "GND_38") (pintype "passive"))
      (node (ref "DD4") (pin "51") (pinfunction "GND_51") (pintype "passive"))
      (node (ref "DD4") (pin "61") (pinfunction "GND_61") (pintype "passive"))
      (node (ref "DD4") (pin "83") (pinfunction "GND_83") (pintype "passive"))
      (node (ref "DD4") (pin "94") (pinfunction "GND_94") (pintype "passive"))
      (node (ref "R10") (pin "1") (pinfunction "1_1") (pintype "passive"))
      (node (ref "R11") (pin "1") (pinfunction "1_1") (pintype "passive"))
      (node (ref "XP2") (pin "2") (pinfunction "2_2") (pintype "passive"))
    )
    (net (code "59") (name "Net-(C59-Pad+)") (class "Default")
      (node (ref "C59") (pin "+") (pinfunction "+_+") (pintype "passive"))
      (node (ref "C94") (pin "2") (pinfunction "2_2") (pintype "passive"))
      (node (ref "DA4") (pin "2") (pinfunction "VOUT_2") (pintype "passive"))
      (node (ref "DA4") (pin "4") (pinfunction "VOUT_4") (pintype "passive"))
      (node (ref "L10") (pin "1") (pinfunction "1_1") (pintype "passive"))
      (node (ref "L9") (pin "1") (pinfunction "1_1") (pintype "passive"))
    )
    (net (code "60") (name "Net-(DA5-DE)") (class "Default")
      (node (ref "DA5") (pin "3") (pinfunction "DE_3") (pintype "passive"))
      (node (ref "R15") (pin "2") (pinfunction "2_2") (pintype "passive"))
    )
    (net (code "61") (name "Net-(DA6-DE)") (class "Default")
      (node (ref "DA6") (pin "3") (pinfunction "DE_3") (pintype "passive"))
      (node (ref "R17") (pin "2") (pinfunction "2_2") (pintype "passive"))
    )
    (net (code "62") (name "Net-(DA7-DE)") (class "Default")
      (node (ref "DA7") (pin "3") (pinfunction "DE_3") (pintype "passive"))
      (node (ref "R19") (pin "2") (pinfunction "2_2") (pintype "passive"))
    )
    (net (code "63") (name "Net-(DA8-DE)") (class "Default")
      (node (ref "DA8") (pin "3") (pinfunction "DE_3") (pintype "passive"))
      (node (ref "R20") (pin "2") (pinfunction "2_2") (pintype "passive"))
    )
    (net (code "64") (name "Net-(DA9-DE)") (class "Default")
      (node (ref "DA9") (pin "3") (pinfunction "DE_3") (pintype "passive"))
      (node (ref "R21") (pin "2") (pinfunction "2_2") (pintype "passive"))
    )
    (net (code "65") (name "Net-(DD4A-PE11)") (class "Default")
      (node (ref "DD4") (pin "64") (pinfunction "PE11_64") (pintype "passive"))
      (node (ref "TP9") (pin "1") (pinfunction "1_1") (pintype "passive"))
    )
    (net (code "66") (name "Net-(DD4A-PE12)") (class "Default")
      (node (ref "DD4") (pin "65") (pinfunction "PE12_65") (pintype "passive"))
      (node (ref "TP8") (pin "1") (pinfunction "1_1") (pintype "passive"))
    )
    (net (code "67") (name "Net-(DD4A-PE13)") (class "Default")
      (node (ref "DD4") (pin "66") (pinfunction "PE13_66") (pintype "passive"))
      (node (ref "TP7") (pin "1") (pinfunction "1_1") (pintype "passive"))
    )
    (net (code "68") (name "Net-(DD4A-PE14)") (class "Default")
      (node (ref "DD4") (pin "54") (pinfunction "PE14_54") (pintype "passive"))
      (node (ref "TP12") (pin "1") (pinfunction "1_1") (pintype "passive"))
    )
    (net (code "69") (name "Net-(DD4A-PE15)") (class "Default")
      (node (ref "DD4") (pin "55") (pinfunction "PE15_55") (pintype "passive"))
      (node (ref "TP11") (pin "1") (pinfunction "1_1") (pintype "passive"))
    )
    (net (code "70") (name "Net-(DD4A-PG0)") (class "Default")
      (node (ref "DD4") (pin "56") (pinfunction "PG0_56") (pintype "passive"))
      (node (ref "TP10") (pin "1") (pinfunction "1_1") (pintype "passive"))
    )
    (net (code "71") (name "Net-(DD4B-BOOT_0)") (class "Default")
      (node (ref "DD4") (pin "138") (pinfunction "BOOT_0_138") (pintype "passive"))
      (node (ref "R10") (pin "2") (pinfunction "2_2") (pintype "passive"))
    )
    (net (code "72") (name "Net-(DD4B-OSK_0)") (class "Default")
      (node (ref "C60") (pin "1") (pinfunction "1_1") (pintype "passive"))
      (node (ref "DD4") (pin "24") (pinfunction "OSK_0_24") (pintype "passive"))
      (node (ref "ZQ1") (pin "1") (pinfunction "1_1") (pintype "passive"))
    )
    (net (code "73") (name "Net-(DD4B-OSK_I)") (class "Default")
      (node (ref "C61") (pin "1") (pinfunction "1_1") (pintype "passive"))
      (node (ref "DD4") (pin "23") (pinfunction "OSK_I_23") (pintype "passive"))
      (node (ref "ZQ1") (pin "3") (pinfunction "3_3") (pintype "passive"))
    )
    (net (code "74") (name "Net-(DD4B-VCAP1)") (class "Default")
      (node (ref "C66") (pin "+") (pinfunction "+_+") (pintype "passive"))
      (node (ref "DD4") (pin "71") (pinfunction "VCAP1_71") (pintype "passive"))
    )
    (net (code "75") (name "Net-(DD4B-VCAP2)") (class "Default")
      (node (ref "C67") (pin "+") (pinfunction "+_+") (pintype "passive"))
      (node (ref "DD4") (pin "106") (pinfunction "VCAP2_106") (pintype "passive"))
    )
    (net (code "76") (name "unconnected-(DA5-RO-Pad1)") (class "Default")
      (node (ref "DA5") (pin "1") (pinfunction "RO_1") (pintype "passive+no_connect"))
    )
    (net (code "77") (name "unconnected-(DA5-~{RE}-Pad2)") (class "Default")
      (node (ref "DA5") (pin "2") (pinfunction "~{RE}_2") (pintype "passive+no_connect"))
    )
    (net (code "78") (name "unconnected-(DA6-RO-Pad1)") (class "Default")
      (node (ref "DA6") (pin "1") (pinfunction "RO_1") (pintype "passive+no_connect"))
    )
    (net (code "79") (name "unconnected-(DA6-~{RE}-Pad2)") (class "Default")
      (node (ref "DA6") (pin "2") (pinfunction "~{RE}_2") (pintype "passive+no_connect"))
    )
    (net (code "80") (name "unconnected-(DA7-RO-Pad1)") (class "Default")
      (node (ref "DA7") (pin "1") (pinfunction "RO_1") (pintype "passive+no_connect"))
    )
    (net (code "81") (name "unconnected-(DA7-~{RE}-Pad2)") (class "Default")
      (node (ref "DA7") (pin "2") (pinfunction "~{RE}_2") (pintype "passive+no_connect"))
    )
    (net (code "82") (name "unconnected-(DA8-RO-Pad1)") (class "Default")
      (node (ref "DA8") (pin "1") (pinfunction "RO_1") (pintype "passive+no_connect"))
    )
    (net (code "83") (name "unconnected-(DA8-~{RE}-Pad2)") (class "Default")
      (node (ref "DA8") (pin "2") (pinfunction "~{RE}_2") (pintype "passive+no_connect"))
    )
    (net (code "84") (name "unconnected-(DA9-RO-Pad1)") (class "Default")
      (node (ref "DA9") (pin "1") (pinfunction "RO_1") (pintype "passive+no_connect"))
    )
    (net (code "85") (name "unconnected-(DA9-~{RE}-Pad2)") (class "Default")
      (node (ref "DA9") (pin "2") (pinfunction "~{RE}_2") (pintype "passive+no_connect"))
    )
    (net (code "86") (name "unconnected-(DD4B-SPI_M0-Pad43)") (class "Default")
      (node (ref "DD4") (pin "43") (pinfunction "SPI_M0_43") (pintype "passive"))
    )
    (net (code "87") (name "unconnected-(DD4B-SPI_MI-Pad42)") (class "Default")
      (node (ref "DD4") (pin "42") (pinfunction "SPI_MI_42") (pintype "passive"))
    )
    (net (code "88") (name "unconnected-(DD4B-SPI_SCK-Pad41)") (class "Default")
      (node (ref "DD4") (pin "41") (pinfunction "SPI_SCK_41") (pintype "passive"))
    )
    (net (code "89") (name "unconnected-(DD4C-PA8-Pad100)") (class "Default")
      (node (ref "DD4") (pin "100") (pinfunction "PA8_100") (pintype "passive"))
    )
    (net (code "90") (name "unconnected-(DD4C-PC10-Pad111)") (class "Default")
      (node (ref "DD4") (pin "111") (pinfunction "PC10_111") (pintype "passive"))
    )
    (net (code "91") (name "unconnected-(DD4C-PC12-Pad113)") (class "Default")
      (node (ref "DD4") (pin "113") (pinfunction "PC12_113") (pintype "passive"))
    )
    (net (code "92") (name "unconnected-(DD4C-PD1-Pad115)") (class "Default")
      (node (ref "DD4") (pin "115") (pinfunction "PD1_115") (pintype "passive"))
    )
    (net (code "93") (name "unconnected-(DD4D-PA0-Pad34)") (class "Default")
      (node (ref "DD4") (pin "34") (pinfunction "PA0_34") (pintype "passive"))
    )
    (net (code "94") (name "unconnected-(DD4D-PA1-Pad35)") (class "Default")
      (node (ref "DD4") (pin "35") (pinfunction "PA1_35") (pintype "passive"))
    )
    (net (code "95") (name "unconnected-(DD4D-PA3-Pad37)") (class "Default")
      (node (ref "DD4") (pin "37") (pinfunction "PA3_37") (pintype "passive"))
    )
    (net (code "96") (name "unconnected-(DD4D-PA4-Pad40)") (class "Default")
      (node (ref "DD4") (pin "40") (pinfunction "PA4_40") (pintype "passive"))
    )
    (net (code "97") (name "unconnected-(DD4D-PA15-Pad110)") (class "Default")
      (node (ref "DD4") (pin "110") (pinfunction "PA15_110") (pintype "passive"))
    )
    (net (code "98") (name "unconnected-(DD4D-PB4-Pad134)") (class "Default")
      (node (ref "DD4") (pin "134") (pinfunction "PB4_134") (pintype "passive"))
    )
    (net (code "99") (name "unconnected-(DD4D-PB5-Pad135)") (class "Default")
      (node (ref "DD4") (pin "135") (pinfunction "PB5_135") (pintype "passive"))
    )
    (net (code "100") (name "unconnected-(DD4D-PB7-Pad137)") (class "Default")
      (node (ref "DD4") (pin "137") (pinfunction "PB7_137") (pintype "passive"))
    )
    (net (code "101") (name "unconnected-(DD4D-PB8-Pad139)") (class "Default")
      (node (ref "DD4") (pin "139") (pinfunction "PB8_139") (pintype "passive"))
    )
    (net (code "102") (name "unconnected-(DD4D-PB9-Pad140)") (class "Default")
      (node (ref "DD4") (pin "140") (pinfunction "PB9_140") (pintype "passive"))
    )
    (net (code "103") (name "unconnected-(DD4D-PB10-Pad69)") (class "Default")
      (node (ref "DD4") (pin "69") (pinfunction "PB10_69") (pintype "passive"))
    )
    (net (code "104") (name "unconnected-(DD4D-PB11-Pad70)") (class "Default")
      (node (ref "DD4") (pin "70") (pinfunction "PB11_70") (pintype "passive"))
    )
    (net (code "105") (name "unconnected-(DD4D-PB12-Pad73)") (class "Default")
      (node (ref "DD4") (pin "73") (pinfunction "PB12_73") (pintype "passive"))
    )
    (net (code "106") (name "unconnected-(DD4D-PB13-Pad74)") (class "Default")
      (node (ref "DD4") (pin "74") (pinfunction "PB13_74") (pintype "passive"))
    )
    (net (code "107") (name "unconnected-(DD4D-PB14-Pad75)") (class "Default")
      (node (ref "DD4") (pin "75") (pinfunction "PB14_75") (pintype "passive"))
    )
    (net (code "108") (name "unconnected-(DD4D-PC6-Pad96)") (class "Default")
      (node (ref "DD4") (pin "96") (pinfunction "PC6_96") (pintype "passive"))
    )
    (net (code "109") (name "unconnected-(DD4D-PC7-Pad97)") (class "Default")
      (node (ref "DD4") (pin "97") (pinfunction "PC7_97") (pintype "passive"))
    )
    (net (code "110") (name "unconnected-(DD4D-PC8-Pad98)") (class "Default")
      (node (ref "DD4") (pin "98") (pinfunction "PC8_98") (pintype "passive"))
    )
    (net (code "111") (name "unconnected-(DD4D-PC9-Pad99)") (class "Default")
      (node (ref "DD4") (pin "99") (pinfunction "PC9_99") (pintype "passive"))
    )
    (net (code "112") (name "unconnected-(DD4D-PC11-Pad112)") (class "Default")
      (node (ref "DD4") (pin "112") (pinfunction "PC11_112") (pintype "passive"))
    )
    (net (code "113") (name "unconnected-(DD4D-PC13-Pad7)") (class "Default")
      (node (ref "DD4") (pin "7") (pinfunction "PC13_7") (pintype "passive"))
    )
    (net (code "114") (name "unconnected-(DD4D-PC14-Pad8)") (class "Default")
      (node (ref "DD4") (pin "8") (pinfunction "PC14_8") (pintype "passive"))
    )
    (net (code "115") (name "unconnected-(DD4D-PD0-Pad114)") (class "Default")
      (node (ref "DD4") (pin "114") (pinfunction "PD0_114") (pintype "passive"))
    )
    (net (code "116") (name "unconnected-(DD4D-PD2-Pad116)") (class "Default")
      (node (ref "DD4") (pin "116") (pinfunction "PD2_116") (pintype "passive"))
    )
    (net (code "117") (name "unconnected-(DD4D-PD3-Pad117)") (class "Default")
      (node (ref "DD4") (pin "117") (pinfunction "PD3_117") (pintype "passive"))
    )
    (net (code "118") (name "unconnected-(DD4D-PD4-Pad118)") (class "Default")
      (node (ref "DD4") (pin "118") (pinfunction "PD4_118") (pintype "passive"))
    )
    (net (code "119") (name "unconnected-(DD4D-PD5-Pad119)") (class "Default")
      (node (ref "DD4") (pin "119") (pinfunction "PD5_119") (pintype "passive"))
    )
    (net (code "120") (name "unconnected-(DD4D-PD6-Pad122)") (class "Default")
      (node (ref "DD4") (pin "122") (pinfunction "PD6_122") (pintype "passive"))
    )
    (net (code "121") (name "unconnected-(DD4D-PD7-Pad123)") (class "Default")
      (node (ref "DD4") (pin "123") (pinfunction "PD7_123") (pintype "passive"))
    )
    (net (code "122") (name "unconnected-(DD4D-PD10-Pad79)") (class "Default")
      (node (ref "DD4") (pin "79") (pinfunction "PD10_79") (pintype "passive"))
    )
    (net (code "123") (name "unconnected-(DD4D-PD14-Pad85)") (class "Default")
      (node (ref "DD4") (pin "85") (pinfunction "PD14_85") (pintype "passive"))
    )
    (net (code "124") (name "unconnected-(DD4D-PD15-Pad86)") (class "Default")
      (node (ref "DD4") (pin "86") (pinfunction "PD15_86") (pintype "passive"))
    )
    (net (code "125") (name "unconnected-(DD4D-PE0-Pad141)") (class "Default")
      (node (ref "DD4") (pin "141") (pinfunction "PE0_141") (pintype "passive"))
    )
    (net (code "126") (name "unconnected-(DD4D-PE1-Pad142)") (class "Default")
      (node (ref "DD4") (pin "142") (pinfunction "PE1_142") (pintype "passive"))
    )
    (net (code "127") (name "unconnected-(DD4D-PE2-Pad1)") (class "Default")
      (node (ref "DD4") (pin "1") (pinfunction "PE2_1") (pintype "passive"))
    )
    (net (code "128") (name "unconnected-(DD4D-PE3-Pad2)") (class "Default")
      (node (ref "DD4") (pin "2") (pinfunction "PE3_2") (pintype "passive"))
    )
    (net (code "129") (name "unconnected-(DD4D-PE4-Pad3)") (class "Default")
      (node (ref "DD4") (pin "3") (pinfunction "PE4_3") (pintype "passive"))
    )
    (net (code "130") (name "unconnected-(DD4D-PE5-Pad4)") (class "Default")
      (node (ref "DD4") (pin "4") (pinfunction "PE5_4") (pintype "passive"))
    )
    (net (code "131") (name "unconnected-(DD4D-PE6-Pad5)") (class "Default")
      (node (ref "DD4") (pin "5") (pinfunction "PE6_5") (pintype "passive"))
    )
    (net (code "132") (name "unconnected-(DD4D-PE8-Pad59)") (class "Default")
      (node (ref "DD4") (pin "59") (pinfunction "PE8_59") (pintype "passive"))
    )
    (net (code "133") (name "unconnected-(DD4D-PE9-Pad60)") (class "Default")
      (node (ref "DD4") (pin "60") (pinfunction "PE9_60") (pintype "passive"))
    )
    (net (code "134") (name "unconnected-(DD4D-PE10-Pad63)") (class "Default")
      (node (ref "DD4") (pin "63") (pinfunction "PE10_63") (pintype "passive"))
    )
    (net (code "135") (name "unconnected-(DD4D-PE14-Pad67)") (class "Default")
      (node (ref "DD4") (pin "67") (pinfunction "PE14_67") (pintype "passive"))
    )
    (net (code "136") (name "unconnected-(DD4D-PE15-Pad68)") (class "Default")
      (node (ref "DD4") (pin "68") (pinfunction "PE15_68") (pintype "passive"))
    )
    (net (code "137") (name "unconnected-(DD4D-PF2-Pad12)") (class "Default")
      (node (ref "DD4") (pin "12") (pinfunction "PF2_12") (pintype "passive"))
    )
    (net (code "138") (name "unconnected-(DD4D-PF3-Pad13)") (class "Default")
      (node (ref "DD4") (pin "13") (pinfunction "PF3_13") (pintype "passive"))
    )
    (net (code "139") (name "unconnected-(DD4D-PF4-Pad14)") (class "Default")
      (node (ref "DD4") (pin "14") (pinfunction "PF4_14") (pintype "passive"))
    )
    (net (code "140") (name "unconnected-(DD4D-PF6-Pad18)") (class "Default")
      (node (ref "DD4") (pin "18") (pinfunction "PF6_18") (pintype "passive"))
    )
    (net (code "141") (name "unconnected-(DD4D-PF13-Pad53)") (class "Default")
      (node (ref "DD4") (pin "53") (pinfunction "PF13_53") (pintype "passive"))
    )
    (net (code "142") (name "unconnected-(DD4D-PG2-Pad87)") (class "Default")
      (node (ref "DD4") (pin "87") (pinfunction "PG2_87") (pintype "passive"))
    )
    (net (code "143") (name "unconnected-(DD4D-PG3-Pad88)") (class "Default")
      (node (ref "DD4") (pin "88") (pinfunction "PG3_88") (pintype "passive"))
    )
    (net (code "144") (name "unconnected-(DD4D-PG9-Pad124)") (class "Default")
      (node (ref "DD4") (pin "124") (pinfunction "PG9_124") (pintype "passive"))
    )
    (net (code "145") (name "unconnected-(DD4D-PG10-Pad125)") (class "Default")
      (node (ref "DD4") (pin "125") (pinfunction "PG10_125") (pintype "passive"))
    )
    (net (code "146") (name "unconnected-(DD4D-PG12-Pad127)") (class "Default")
      (node (ref "DD4") (pin "127") (pinfunction "PG12_127") (pintype "passive"))
    )
    (net (code "147") (name "unconnected-(DD4D-PG13-Pad128)") (class "Default")
      (node (ref "DD4") (pin "128") (pinfunction "PG13_128") (pintype "passive"))
    )
    (net (code "148") (name "unconnected-(DD4D-PG14-Pad129)") (class "Default")
      (node (ref "DD4") (pin "129") (pinfunction "PG14_129") (pintype "passive"))
    )
    (net (code "149") (name "unconnected-(DD4D-PG15-Pad132)") (class "Default")
      (node (ref "DD4") (pin "132") (pinfunction "PG15_132") (pintype "passive"))
    )
    (net (code "150") (name "unconnected-(DD4D-VREF+-Pad32)") (class "Default")
      (node (ref "DD4") (pin "32") (pinfunction "VREF+_32") (pintype "passive"))
    )
  )
)
